# sec_board.net
KiCad netlist of a schematic drawn in EAGLE
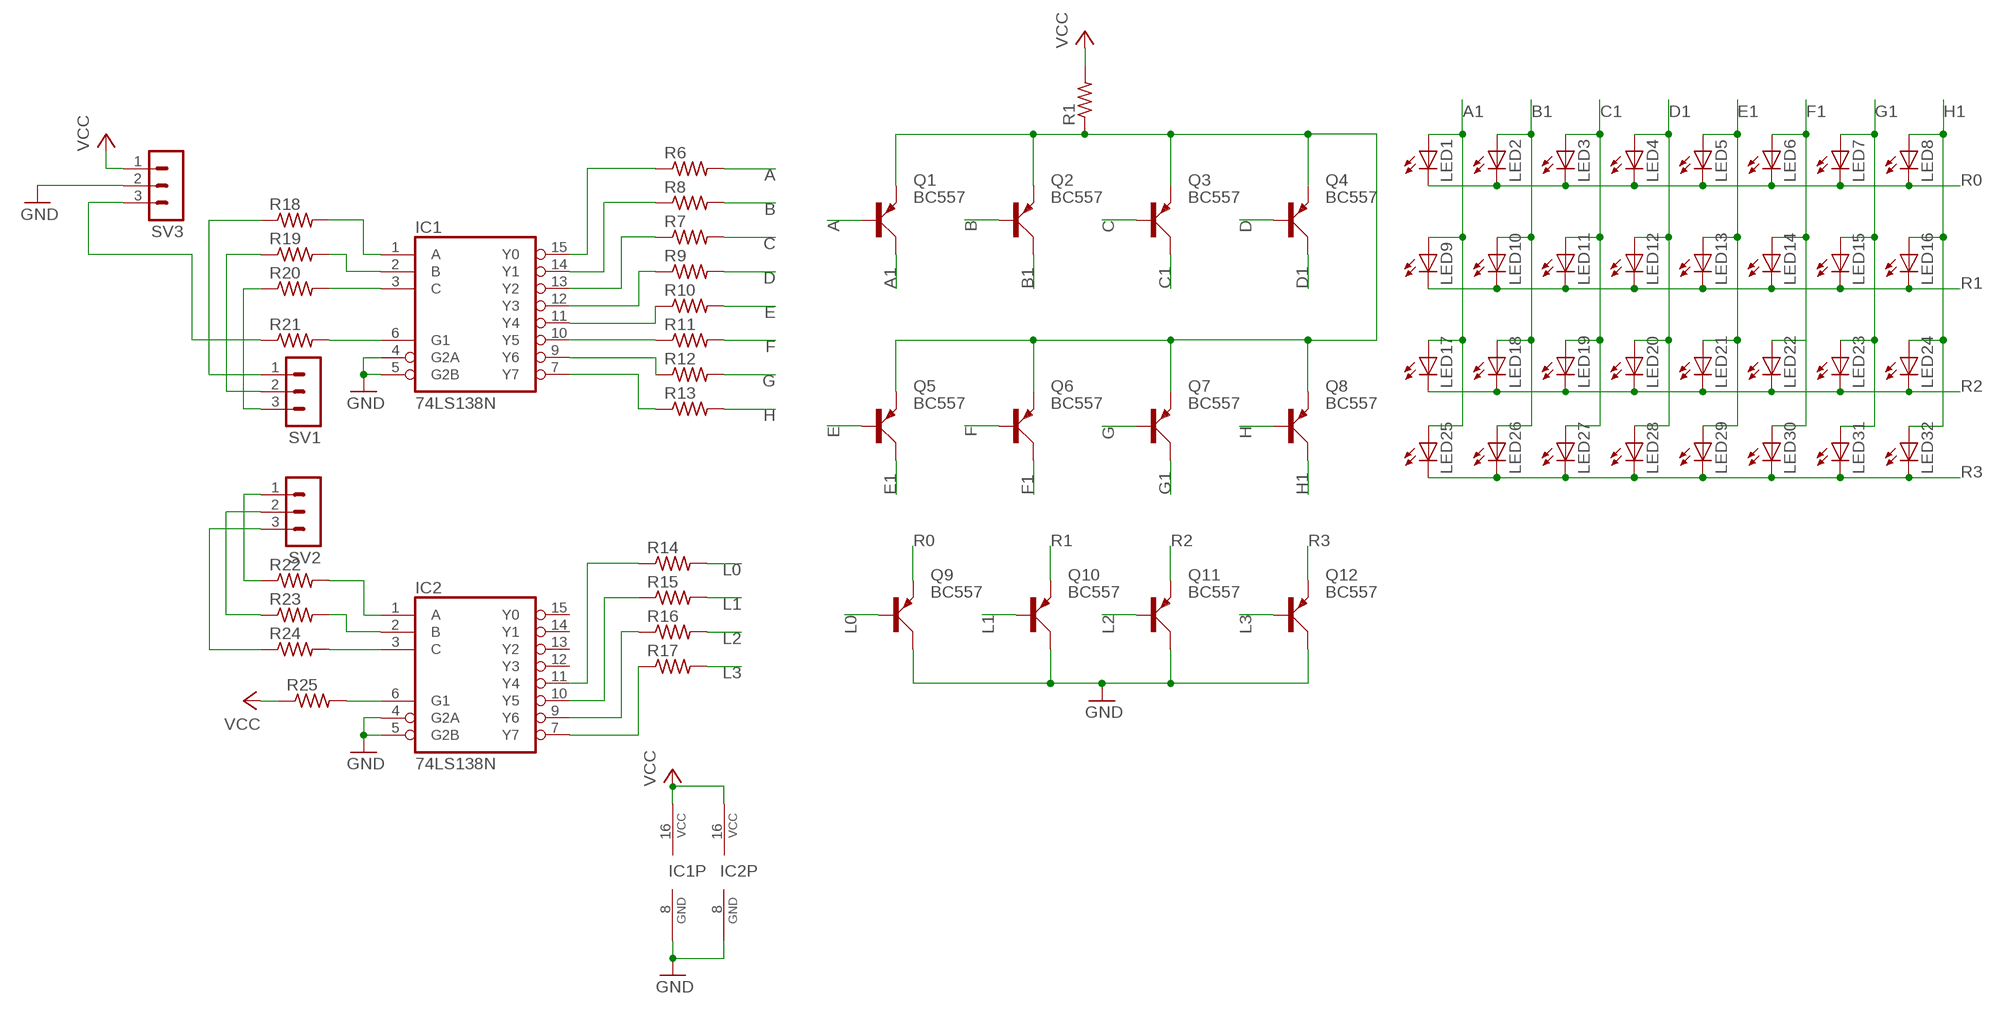
[diagram p0: schematic, sheet 1]

(export (version "E")
  (design (tool "Eeschema 10.0.6"))
  (components
    (comp (ref "IC1")
      (value "74LS138N")
      (footprint "eagle-import:DIL16")
      (libsource (lib "eagle-import") (part "74138NLS"))
    )
    (comp (ref "IC2")
      (value "74LS138N")
      (footprint "eagle-import:DIL16")
      (libsource (lib "eagle-import") (part "74138NLS"))
    )
    (comp (ref "LED1")
      (value "LED5MM")
      (footprint "eagle-import:LED5MM")
      (libsource (lib "eagle-import") (part "LED5MM"))
    )
    (comp (ref "LED2")
      (value "LED5MM")
      (footprint "eagle-import:LED5MM")
      (libsource (lib "eagle-import") (part "LED5MM"))
    )
    (comp (ref "LED3")
      (value "LED5MM")
      (footprint "eagle-import:LED5MM")
      (libsource (lib "eagle-import") (part "LED5MM"))
    )
    (comp (ref "LED4")
      (value "LED5MM")
      (footprint "eagle-import:LED5MM")
      (libsource (lib "eagle-import") (part "LED5MM"))
    )
    (comp (ref "LED5")
      (value "LED5MM")
      (footprint "eagle-import:LED5MM")
      (libsource (lib "eagle-import") (part "LED5MM"))
    )
    (comp (ref "LED6")
      (value "LED5MM")
      (footprint "eagle-import:LED5MM")
      (libsource (lib "eagle-import") (part "LED5MM"))
    )
    (comp (ref "LED7")
      (value "LED5MM")
      (footprint "eagle-import:LED5MM")
      (libsource (lib "eagle-import") (part "LED5MM"))
    )
    (comp (ref "LED8")
      (value "LED5MM")
      (footprint "eagle-import:LED5MM")
      (libsource (lib "eagle-import") (part "LED5MM"))
    )
    (comp (ref "LED9")
      (value "LED5MM")
      (footprint "eagle-import:LED5MM")
      (libsource (lib "eagle-import") (part "LED5MM"))
    )
    (comp (ref "LED10")
      (value "LED5MM")
      (footprint "eagle-import:LED5MM")
      (libsource (lib "eagle-import") (part "LED5MM"))
    )
    (comp (ref "LED11")
      (value "LED5MM")
      (footprint "eagle-import:LED5MM")
      (libsource (lib "eagle-import") (part "LED5MM"))
    )
    (comp (ref "LED12")
      (value "LED5MM")
      (footprint "eagle-import:LED5MM")
      (libsource (lib "eagle-import") (part "LED5MM"))
    )
    (comp (ref "LED13")
      (value "LED5MM")
      (footprint "eagle-import:LED5MM")
      (libsource (lib "eagle-import") (part "LED5MM"))
    )
    (comp (ref "LED14")
      (value "LED5MM")
      (footprint "eagle-import:LED5MM")
      (libsource (lib "eagle-import") (part "LED5MM"))
    )
    (comp (ref "LED15")
      (value "LED5MM")
      (footprint "eagle-import:LED5MM")
      (libsource (lib "eagle-import") (part "LED5MM"))
    )
    (comp (ref "LED16")
      (value "LED5MM")
      (footprint "eagle-import:LED5MM")
      (libsource (lib "eagle-import") (part "LED5MM"))
    )
    (comp (ref "LED17")
      (value "LED5MM")
      (footprint "eagle-import:LED5MM")
      (libsource (lib "eagle-import") (part "LED5MM"))
    )
    (comp (ref "LED18")
      (value "LED5MM")
      (footprint "eagle-import:LED5MM")
      (libsource (lib "eagle-import") (part "LED5MM"))
    )
    (comp (ref "LED19")
      (value "LED5MM")
      (footprint "eagle-import:LED5MM")
      (libsource (lib "eagle-import") (part "LED5MM"))
    )
    (comp (ref "LED20")
      (value "LED5MM")
      (footprint "eagle-import:LED5MM")
      (libsource (lib "eagle-import") (part "LED5MM"))
    )
    (comp (ref "LED21")
      (value "LED5MM")
      (footprint "eagle-import:LED5MM")
      (libsource (lib "eagle-import") (part "LED5MM"))
    )
    (comp (ref "LED22")
      (value "LED5MM")
      (footprint "eagle-import:LED5MM")
      (libsource (lib "eagle-import") (part "LED5MM"))
    )
    (comp (ref "LED23")
      (value "LED5MM")
      (footprint "eagle-import:LED5MM")
      (libsource (lib "eagle-import") (part "LED5MM"))
    )
    (comp (ref "LED24")
      (value "LED5MM")
      (footprint "eagle-import:LED5MM")
      (libsource (lib "eagle-import") (part "LED5MM"))
    )
    (comp (ref "LED25")
      (value "LED5MM")
      (footprint "eagle-import:LED5MM")
      (libsource (lib "eagle-import") (part "LED5MM"))
    )
    (comp (ref "LED26")
      (value "LED5MM")
      (footprint "eagle-import:LED5MM")
      (libsource (lib "eagle-import") (part "LED5MM"))
    )
    (comp (ref "LED27")
      (value "LED5MM")
      (footprint "eagle-import:LED5MM")
      (libsource (lib "eagle-import") (part "LED5MM"))
    )
    (comp (ref "LED28")
      (value "LED5MM")
      (footprint "eagle-import:LED5MM")
      (libsource (lib "eagle-import") (part "LED5MM"))
    )
    (comp (ref "LED29")
      (value "LED5MM")
      (footprint "eagle-import:LED5MM")
      (libsource (lib "eagle-import") (part "LED5MM"))
    )
    (comp (ref "LED30")
      (value "LED5MM")
      (footprint "eagle-import:LED5MM")
      (libsource (lib "eagle-import") (part "LED5MM"))
    )
    (comp (ref "LED31")
      (value "LED5MM")
      (footprint "eagle-import:LED5MM")
      (libsource (lib "eagle-import") (part "LED5MM"))
    )
    (comp (ref "LED32")
      (value "LED5MM")
      (footprint "eagle-import:LED5MM")
      (libsource (lib "eagle-import") (part "LED5MM"))
    )
    (comp (ref "Q1")
      (value "BC557")
      (footprint "eagle-import:SOT54A")
      (libsource (lib "eagle-import") (part "BC557"))
    )
    (comp (ref "Q2")
      (value "BC557")
      (footprint "eagle-import:SOT54A")
      (libsource (lib "eagle-import") (part "BC557"))
    )
    (comp (ref "Q3")
      (value "BC557")
      (footprint "eagle-import:SOT54A")
      (libsource (lib "eagle-import") (part "BC557"))
    )
    (comp (ref "Q4")
      (value "BC557")
      (footprint "eagle-import:SOT54A")
      (libsource (lib "eagle-import") (part "BC557"))
    )
    (comp (ref "Q5")
      (value "BC557")
      (footprint "eagle-import:SOT54A")
      (libsource (lib "eagle-import") (part "BC557"))
    )
    (comp (ref "Q6")
      (value "BC557")
      (footprint "eagle-import:SOT54A")
      (libsource (lib "eagle-import") (part "BC557"))
    )
    (comp (ref "Q7")
      (value "BC557")
      (footprint "eagle-import:SOT54A")
      (libsource (lib "eagle-import") (part "BC557"))
    )
    (comp (ref "Q8")
      (value "BC557")
      (footprint "eagle-import:SOT54A")
      (libsource (lib "eagle-import") (part "BC557"))
    )
    (comp (ref "Q9")
      (value "BC557")
      (footprint "eagle-import:SOT54A")
      (libsource (lib "eagle-import") (part "BC557"))
    )
    (comp (ref "Q10")
      (value "BC557")
      (footprint "eagle-import:SOT54A")
      (libsource (lib "eagle-import") (part "BC557"))
    )
    (comp (ref "Q11")
      (value "BC557")
      (footprint "eagle-import:SOT54A")
      (libsource (lib "eagle-import") (part "BC557"))
    )
    (comp (ref "Q12")
      (value "BC557")
      (footprint "eagle-import:SOT54A")
      (libsource (lib "eagle-import") (part "BC557"))
    )
    (comp (ref "R1")
      (value "R-US_R0805")
      (footprint "eagle-import:R0805")
      (libsource (lib "eagle-import") (part "R-US_R0805"))
    )
    (comp (ref "R6")
      (value "R-US_R0805")
      (footprint "eagle-import:R0805")
      (libsource (lib "eagle-import") (part "R-US_R0805"))
    )
    (comp (ref "R7")
      (value "R-US_R0805")
      (footprint "eagle-import:R0805")
      (libsource (lib "eagle-import") (part "R-US_R0805"))
    )
    (comp (ref "R8")
      (value "R-US_R0805")
      (footprint "eagle-import:R0805")
      (libsource (lib "eagle-import") (part "R-US_R0805"))
    )
    (comp (ref "R9")
      (value "R-US_R0805")
      (footprint "eagle-import:R0805")
      (libsource (lib "eagle-import") (part "R-US_R0805"))
    )
    (comp (ref "R10")
      (value "R-US_R0805")
      (footprint "eagle-import:R0805")
      (libsource (lib "eagle-import") (part "R-US_R0805"))
    )
    (comp (ref "R11")
      (value "R-US_R0805")
      (footprint "eagle-import:R0805")
      (libsource (lib "eagle-import") (part "R-US_R0805"))
    )
    (comp (ref "R12")
      (value "R-US_R0805")
      (footprint "eagle-import:R0805")
      (libsource (lib "eagle-import") (part "R-US_R0805"))
    )
    (comp (ref "R13")
      (value "R-US_R0805")
      (footprint "eagle-import:R0805")
      (libsource (lib "eagle-import") (part "R-US_R0805"))
    )
    (comp (ref "R14")
      (value "R-US_R0805")
      (footprint "eagle-import:R0805")
      (libsource (lib "eagle-import") (part "R-US_R0805"))
    )
    (comp (ref "R15")
      (value "R-US_R0805")
      (footprint "eagle-import:R0805")
      (libsource (lib "eagle-import") (part "R-US_R0805"))
    )
    (comp (ref "R16")
      (value "R-US_R0805")
      (footprint "eagle-import:R0805")
      (libsource (lib "eagle-import") (part "R-US_R0805"))
    )
    (comp (ref "R17")
      (value "R-US_R0805")
      (footprint "eagle-import:R0805")
      (libsource (lib "eagle-import") (part "R-US_R0805"))
    )
    (comp (ref "R18")
      (value "R-US_M0805")
      (footprint "eagle-import:M0805")
      (libsource (lib "eagle-import") (part "resistor_348_R-US_M0805"))
    )
    (comp (ref "R19")
      (value "R-US_M0805")
      (footprint "eagle-import:M0805")
      (libsource (lib "eagle-import") (part "resistor_348_R-US_M0805"))
    )
    (comp (ref "R20")
      (value "R-US_M0805")
      (footprint "eagle-import:M0805")
      (libsource (lib "eagle-import") (part "resistor_348_R-US_M0805"))
    )
    (comp (ref "R21")
      (value "R-US_M0805")
      (footprint "eagle-import:M0805")
      (libsource (lib "eagle-import") (part "resistor_348_R-US_M0805"))
    )
    (comp (ref "R22")
      (value "R-US_M0805")
      (footprint "eagle-import:M0805")
      (libsource (lib "eagle-import") (part "resistor_348_R-US_M0805"))
    )
    (comp (ref "R23")
      (value "R-US_M0805")
      (footprint "eagle-import:M0805")
      (libsource (lib "eagle-import") (part "resistor_348_R-US_M0805"))
    )
    (comp (ref "R24")
      (value "R-US_M0805")
      (footprint "eagle-import:M0805")
      (libsource (lib "eagle-import") (part "resistor_348_R-US_M0805"))
    )
    (comp (ref "R25")
      (value "R-US_M0805")
      (footprint "eagle-import:M0805")
      (libsource (lib "eagle-import") (part "resistor_348_R-US_M0805"))
    )
    (comp (ref "SV1")
      (value "MA03-1")
      (footprint "eagle-import:MA03-1")
      (libsource (lib "eagle-import") (part "MA03-1"))
    )
    (comp (ref "SV2")
      (value "MA03-1")
      (footprint "eagle-import:MA03-1")
      (libsource (lib "eagle-import") (part "MA03-1"))
    )
    (comp (ref "SV3")
      (value "MA03-1")
      (footprint "eagle-import:MA03-1")
      (libsource (lib "eagle-import") (part "MA03-1"))
    )
  )
  (nets
    (net (code "1") (name "/A") (class "Default")
      (node (ref "Q1") (pin "B") (pinfunction "B_B") (pintype "passive"))
      (node (ref "R6") (pin "2") (pinfunction "2_2") (pintype "passive"))
    )
    (net (code "2") (name "/A1") (class "Default")
      (node (ref "LED1") (pin "A") (pinfunction "A_A") (pintype "passive"))
      (node (ref "LED17") (pin "A") (pinfunction "A_A") (pintype "passive"))
      (node (ref "LED25") (pin "A") (pinfunction "A_A") (pintype "passive"))
      (node (ref "LED9") (pin "A") (pinfunction "A_A") (pintype "passive"))
      (node (ref "Q1") (pin "C") (pinfunction "C_C") (pintype "passive"))
    )
    (net (code "3") (name "/B") (class "Default")
      (node (ref "Q2") (pin "B") (pinfunction "B_B") (pintype "passive"))
      (node (ref "R8") (pin "2") (pinfunction "2_2") (pintype "passive"))
    )
    (net (code "4") (name "/B1") (class "Default")
      (node (ref "LED10") (pin "A") (pinfunction "A_A") (pintype "passive"))
      (node (ref "LED18") (pin "A") (pinfunction "A_A") (pintype "passive"))
      (node (ref "LED2") (pin "A") (pinfunction "A_A") (pintype "passive"))
      (node (ref "LED26") (pin "A") (pinfunction "A_A") (pintype "passive"))
      (node (ref "Q2") (pin "C") (pinfunction "C_C") (pintype "passive"))
    )
    (net (code "5") (name "/C") (class "Default")
      (node (ref "Q3") (pin "B") (pinfunction "B_B") (pintype "passive"))
      (node (ref "R7") (pin "2") (pinfunction "2_2") (pintype "passive"))
    )
    (net (code "6") (name "/C1") (class "Default")
      (node (ref "LED11") (pin "A") (pinfunction "A_A") (pintype "passive"))
      (node (ref "LED19") (pin "A") (pinfunction "A_A") (pintype "passive"))
      (node (ref "LED27") (pin "A") (pinfunction "A_A") (pintype "passive"))
      (node (ref "LED3") (pin "A") (pinfunction "A_A") (pintype "passive"))
      (node (ref "Q3") (pin "C") (pinfunction "C_C") (pintype "passive"))
    )
    (net (code "7") (name "/D") (class "Default")
      (node (ref "Q4") (pin "B") (pinfunction "B_B") (pintype "passive"))
      (node (ref "R9") (pin "2") (pinfunction "2_2") (pintype "passive"))
    )
    (net (code "8") (name "/D1") (class "Default")
      (node (ref "LED12") (pin "A") (pinfunction "A_A") (pintype "passive"))
      (node (ref "LED20") (pin "A") (pinfunction "A_A") (pintype "passive"))
      (node (ref "LED28") (pin "A") (pinfunction "A_A") (pintype "passive"))
      (node (ref "LED4") (pin "A") (pinfunction "A_A") (pintype "passive"))
      (node (ref "Q4") (pin "C") (pinfunction "C_C") (pintype "passive"))
    )
    (net (code "9") (name "/E") (class "Default")
      (node (ref "Q5") (pin "B") (pinfunction "B_B") (pintype "passive"))
      (node (ref "R10") (pin "2") (pinfunction "2_2") (pintype "passive"))
    )
    (net (code "10") (name "/E1") (class "Default")
      (node (ref "LED13") (pin "A") (pinfunction "A_A") (pintype "passive"))
      (node (ref "LED21") (pin "A") (pinfunction "A_A") (pintype "passive"))
      (node (ref "LED29") (pin "A") (pinfunction "A_A") (pintype "passive"))
      (node (ref "LED5") (pin "A") (pinfunction "A_A") (pintype "passive"))
      (node (ref "Q5") (pin "C") (pinfunction "C_C") (pintype "passive"))
    )
    (net (code "11") (name "/F") (class "Default")
      (node (ref "Q6") (pin "B") (pinfunction "B_B") (pintype "passive"))
      (node (ref "R11") (pin "2") (pinfunction "2_2") (pintype "passive"))
    )
    (net (code "12") (name "/F1") (class "Default")
      (node (ref "LED14") (pin "A") (pinfunction "A_A") (pintype "passive"))
      (node (ref "LED22") (pin "A") (pinfunction "A_A") (pintype "passive"))
      (node (ref "LED30") (pin "A") (pinfunction "A_A") (pintype "passive"))
      (node (ref "LED6") (pin "A") (pinfunction "A_A") (pintype "passive"))
      (node (ref "Q6") (pin "C") (pinfunction "C_C") (pintype "passive"))
    )
    (net (code "13") (name "/G") (class "Default")
      (node (ref "Q7") (pin "B") (pinfunction "B_B") (pintype "passive"))
      (node (ref "R12") (pin "2") (pinfunction "2_2") (pintype "passive"))
    )
    (net (code "14") (name "/G1") (class "Default")
      (node (ref "LED15") (pin "A") (pinfunction "A_A") (pintype "passive"))
      (node (ref "LED23") (pin "A") (pinfunction "A_A") (pintype "passive"))
      (node (ref "LED31") (pin "A") (pinfunction "A_A") (pintype "passive"))
      (node (ref "LED7") (pin "A") (pinfunction "A_A") (pintype "passive"))
      (node (ref "Q7") (pin "C") (pinfunction "C_C") (pintype "passive"))
    )
    (net (code "15") (name "/H") (class "Default")
      (node (ref "Q8") (pin "B") (pinfunction "B_B") (pintype "passive"))
      (node (ref "R13") (pin "2") (pinfunction "2_2") (pintype "passive"))
    )
    (net (code "16") (name "/H1") (class "Default")
      (node (ref "LED16") (pin "A") (pinfunction "A_A") (pintype "passive"))
      (node (ref "LED24") (pin "A") (pinfunction "A_A") (pintype "passive"))
      (node (ref "LED32") (pin "A") (pinfunction "A_A") (pintype "passive"))
      (node (ref "LED8") (pin "A") (pinfunction "A_A") (pintype "passive"))
      (node (ref "Q8") (pin "C") (pinfunction "C_C") (pintype "passive"))
    )
    (net (code "17") (name "/L0") (class "Default")
      (node (ref "Q9") (pin "B") (pinfunction "B_B") (pintype "passive"))
      (node (ref "R14") (pin "2") (pinfunction "2_2") (pintype "passive"))
    )
    (net (code "18") (name "/L1") (class "Default")
      (node (ref "Q10") (pin "B") (pinfunction "B_B") (pintype "passive"))
      (node (ref "R15") (pin "2") (pinfunction "2_2") (pintype "passive"))
    )
    (net (code "19") (name "/L2") (class "Default")
      (node (ref "Q11") (pin "B") (pinfunction "B_B") (pintype "passive"))
      (node (ref "R16") (pin "2") (pinfunction "2_2") (pintype "passive"))
    )
    (net (code "20") (name "/L3") (class "Default")
      (node (ref "Q12") (pin "B") (pinfunction "B_B") (pintype "passive"))
      (node (ref "R17") (pin "2") (pinfunction "2_2") (pintype "passive"))
    )
    (net (code "21") (name "/R0") (class "Default")
      (node (ref "LED1") (pin "K") (pinfunction "C_K") (pintype "passive"))
      (node (ref "LED2") (pin "K") (pinfunction "C_K") (pintype "passive"))
      (node (ref "LED3") (pin "K") (pinfunction "C_K") (pintype "passive"))
      (node (ref "LED4") (pin "K") (pinfunction "C_K") (pintype "passive"))
      (node (ref "LED5") (pin "K") (pinfunction "C_K") (pintype "passive"))
      (node (ref "LED6") (pin "K") (pinfunction "C_K") (pintype "passive"))
      (node (ref "LED7") (pin "K") (pinfunction "C_K") (pintype "passive"))
      (node (ref "LED8") (pin "K") (pinfunction "C_K") (pintype "passive"))
      (node (ref "Q9") (pin "E") (pinfunction "E_E") (pintype "passive"))
    )
    (net (code "22") (name "/R1") (class "Default")
      (node (ref "LED10") (pin "K") (pinfunction "C_K") (pintype "passive"))
      (node (ref "LED11") (pin "K") (pinfunction "C_K") (pintype "passive"))
      (node (ref "LED12") (pin "K") (pinfunction "C_K") (pintype "passive"))
      (node (ref "LED13") (pin "K") (pinfunction "C_K") (pintype "passive"))
      (node (ref "LED14") (pin "K") (pinfunction "C_K") (pintype "passive"))
      (node (ref "LED15") (pin "K") (pinfunction "C_K") (pintype "passive"))
      (node (ref "LED16") (pin "K") (pinfunction "C_K") (pintype "passive"))
      (node (ref "LED9") (pin "K") (pinfunction "C_K") (pintype "passive"))
      (node (ref "Q10") (pin "E") (pinfunction "E_E") (pintype "passive"))
    )
    (net (code "23") (name "/R2") (class "Default")
      (node (ref "LED17") (pin "K") (pinfunction "C_K") (pintype "passive"))
      (node (ref "LED18") (pin "K") (pinfunction "C_K") (pintype "passive"))
      (node (ref "LED19") (pin "K") (pinfunction "C_K") (pintype "passive"))
      (node (ref "LED20") (pin "K") (pinfunction "C_K") (pintype "passive"))
      (node (ref "LED21") (pin "K") (pinfunction "C_K") (pintype "passive"))
      (node (ref "LED22") (pin "K") (pinfunction "C_K") (pintype "passive"))
      (node (ref "LED23") (pin "K") (pinfunction "C_K") (pintype "passive"))
      (node (ref "LED24") (pin "K") (pinfunction "C_K") (pintype "passive"))
      (node (ref "Q11") (pin "E") (pinfunction "E_E") (pintype "passive"))
    )
    (net (code "24") (name "/R3") (class "Default")
      (node (ref "LED25") (pin "K") (pinfunction "C_K") (pintype "passive"))
      (node (ref "LED26") (pin "K") (pinfunction "C_K") (pintype "passive"))
      (node (ref "LED27") (pin "K") (pinfunction "C_K") (pintype "passive"))
      (node (ref "LED28") (pin "K") (pinfunction "C_K") (pintype "passive"))
      (node (ref "LED29") (pin "K") (pinfunction "C_K") (pintype "passive"))
      (node (ref "LED30") (pin "K") (pinfunction "C_K") (pintype "passive"))
      (node (ref "LED31") (pin "K") (pinfunction "C_K") (pintype "passive"))
      (node (ref "LED32") (pin "K") (pinfunction "C_K") (pintype "passive"))
      (node (ref "Q12") (pin "E") (pinfunction "E_E") (pintype "passive"))
    )
    (net (code "25") (name "GND") (class "Default")
      (node (ref "IC1") (pin "4") (pinfunction "G2A_4") (pintype "input"))
      (node (ref "IC1") (pin "5") (pinfunction "G2B_5") (pintype "input"))
      (node (ref "IC1") (pin "8") (pinfunction "GND_8") (pintype "power_in"))
      (node (ref "IC2") (pin "4") (pinfunction "G2A_4") (pintype "input"))
      (node (ref "IC2") (pin "5") (pinfunction "G2B_5") (pintype "input"))
      (node (ref "IC2") (pin "8") (pinfunction "GND_8") (pintype "power_in"))
      (node (ref "Q10") (pin "C") (pinfunction "C_C") (pintype "passive"))
      (node (ref "Q11") (pin "C") (pinfunction "C_C") (pintype "passive"))
      (node (ref "Q12") (pin "C") (pinfunction "C_C") (pintype "passive"))
      (node (ref "Q9") (pin "C") (pinfunction "C_C") (pintype "passive"))
      (node (ref "SV3") (pin "2") (pinfunction "2_2") (pintype "passive"))
    )
    (net (code "26") (name "Net-(IC1A-A)") (class "Default")
      (node (ref "IC1") (pin "1") (pinfunction "A_1") (pintype "input"))
      (node (ref "R18") (pin "2") (pinfunction "2_2") (pintype "passive"))
    )
    (net (code "27") (name "Net-(IC1A-B)") (class "Default")
      (node (ref "IC1") (pin "2") (pinfunction "B_2") (pintype "input"))
      (node (ref "R19") (pin "2") (pinfunction "2_2") (pintype "passive"))
    )
    (net (code "28") (name "Net-(IC1A-C)") (class "Default")
      (node (ref "IC1") (pin "3") (pinfunction "C_3") (pintype "input"))
      (node (ref "R20") (pin "2") (pinfunction "2_2") (pintype "passive"))
    )
    (net (code "29") (name "Net-(IC1A-G1)") (class "Default")
      (node (ref "IC1") (pin "6") (pinfunction "G1_6") (pintype "input"))
      (node (ref "R21") (pin "2") (pinfunction "2_2") (pintype "passive"))
    )
    (net (code "30") (name "Net-(IC1A-Y0)") (class "Default")
      (node (ref "IC1") (pin "15") (pinfunction "Y0_15") (pintype "output"))
      (node (ref "R6") (pin "1") (pinfunction "1_1") (pintype "passive"))
    )
    (net (code "31") (name "Net-(IC1A-Y1)") (class "Default")
      (node (ref "IC1") (pin "14") (pinfunction "Y1_14") (pintype "output"))
      (node (ref "R8") (pin "1") (pinfunction "1_1") (pintype "passive"))
    )
    (net (code "32") (name "Net-(IC1A-Y2)") (class "Default")
      (node (ref "IC1") (pin "13") (pinfunction "Y2_13") (pintype "output"))
      (node (ref "R7") (pin "1") (pinfunction "1_1") (pintype "passive"))
    )
    (net (code "33") (name "Net-(IC1A-Y3)") (class "Default")
      (node (ref "IC1") (pin "12") (pinfunction "Y3_12") (pintype "output"))
      (node (ref "R9") (pin "1") (pinfunction "1_1") (pintype "passive"))
    )
    (net (code "34") (name "Net-(IC1A-Y4)") (class "Default")
      (node (ref "IC1") (pin "11") (pinfunction "Y4_11") (pintype "output"))
      (node (ref "R10") (pin "1") (pinfunction "1_1") (pintype "passive"))
    )
    (net (code "35") (name "Net-(IC1A-Y5)") (class "Default")
      (node (ref "IC1") (pin "10") (pinfunction "Y5_10") (pintype "output"))
      (node (ref "R11") (pin "1") (pinfunction "1_1") (pintype "passive"))
    )
    (net (code "36") (name "Net-(IC1A-Y6)") (class "Default")
      (node (ref "IC1") (pin "9") (pinfunction "Y6_9") (pintype "output"))
      (node (ref "R12") (pin "1") (pinfunction "1_1") (pintype "passive"))
    )
    (net (code "37") (name "Net-(IC1A-Y7)") (class "Default")
      (node (ref "IC1") (pin "7") (pinfunction "Y7_7") (pintype "output"))
      (node (ref "R13") (pin "1") (pinfunction "1_1") (pintype "passive"))
    )
    (net (code "38") (name "Net-(IC2A-A)") (class "Default")
      (node (ref "IC2") (pin "1") (pinfunction "A_1") (pintype "input"))
      (node (ref "R22") (pin "2") (pinfunction "2_2") (pintype "passive"))
    )
    (net (code "39") (name "Net-(IC2A-B)") (class "Default")
      (node (ref "IC2") (pin "2") (pinfunction "B_2") (pintype "input"))
      (node (ref "R23") (pin "2") (pinfunction "2_2") (pintype "passive"))
    )
    (net (code "40") (name "Net-(IC2A-C)") (class "Default")
      (node (ref "IC2") (pin "3") (pinfunction "C_3") (pintype "input"))
      (node (ref "R24") (pin "2") (pinfunction "2_2") (pintype "passive"))
    )
    (net (code "41") (name "Net-(IC2A-G1)") (class "Default")
      (node (ref "IC2") (pin "6") (pinfunction "G1_6") (pintype "input"))
      (node (ref "R25") (pin "2") (pinfunction "2_2") (pintype "passive"))
    )
    (net (code "42") (name "Net-(IC2A-Y4)") (class "Default")
      (node (ref "IC2") (pin "11") (pinfunction "Y4_11") (pintype "output"))
      (node (ref "R14") (pin "1") (pinfunction "1_1") (pintype "passive"))
    )
    (net (code "43") (name "Net-(IC2A-Y5)") (class "Default")
      (node (ref "IC2") (pin "10") (pinfunction "Y5_10") (pintype "output"))
      (node (ref "R15") (pin "1") (pinfunction "1_1") (pintype "passive"))
    )
    (net (code "44") (name "Net-(IC2A-Y6)") (class "Default")
      (node (ref "IC2") (pin "9") (pinfunction "Y6_9") (pintype "output"))
      (node (ref "R16") (pin "1") (pinfunction "1_1") (pintype "passive"))
    )
    (net (code "45") (name "Net-(IC2A-Y7)") (class "Default")
      (node (ref "IC2") (pin "7") (pinfunction "Y7_7") (pintype "output"))
      (node (ref "R17") (pin "1") (pinfunction "1_1") (pintype "passive"))
    )
    (net (code "46") (name "Net-(Q1-PadE)") (class "Default")
      (node (ref "Q1") (pin "E") (pinfunction "E_E") (pintype "passive"))
      (node (ref "Q2") (pin "E") (pinfunction "E_E") (pintype "passive"))
      (node (ref "Q3") (pin "E") (pinfunction "E_E") (pintype "passive"))
      (node (ref "Q4") (pin "E") (pinfunction "E_E") (pintype "passive"))
      (node (ref "Q5") (pin "E") (pinfunction "E_E") (pintype "passive"))
      (node (ref "Q6") (pin "E") (pinfunction "E_E") (pintype "passive"))
      (node (ref "Q7") (pin "E") (pinfunction "E_E") (pintype "passive"))
      (node (ref "Q8") (pin "E") (pinfunction "E_E") (pintype "passive"))
      (node (ref "R1") (pin "1") (pinfunction "1_1") (pintype "passive"))
    )
    (net (code "47") (name "Net-(R18-Pad1)") (class "Default")
      (node (ref "R18") (pin "1") (pinfunction "1_1") (pintype "passive"))
      (node (ref "SV1") (pin "1") (pinfunction "1_1") (pintype "passive"))
    )
    (net (code "48") (name "Net-(R19-Pad1)") (class "Default")
      (node (ref "R19") (pin "1") (pinfunction "1_1") (pintype "passive"))
      (node (ref "SV1") (pin "2") (pinfunction "2_2") (pintype "passive"))
    )
    (net (code "49") (name "Net-(R20-Pad1)") (class "Default")
      (node (ref "R20") (pin "1") (pinfunction "1_1") (pintype "passive"))
      (node (ref "SV1") (pin "3") (pinfunction "3_3") (pintype "passive"))
    )
    (net (code "50") (name "Net-(R21-Pad1)") (class "Default")
      (node (ref "R21") (pin "1") (pinfunction "1_1") (pintype "passive"))
      (node (ref "SV3") (pin "3") (pinfunction "3_3") (pintype "passive"))
    )
    (net (code "51") (name "Net-(R22-Pad1)") (class "Default")
      (node (ref "R22") (pin "1") (pinfunction "1_1") (pintype "passive"))
      (node (ref "SV2") (pin "1") (pinfunction "1_1") (pintype "passive"))
    )
    (net (code "52") (name "Net-(R23-Pad1)") (class "Default")
      (node (ref "R23") (pin "1") (pinfunction "1_1") (pintype "passive"))
      (node (ref "SV2") (pin "2") (pinfunction "2_2") (pintype "passive"))
    )
    (net (code "53") (name "Net-(R24-Pad1)") (class "Default")
      (node (ref "R24") (pin "1") (pinfunction "1_1") (pintype "passive"))
      (node (ref "SV2") (pin "3") (pinfunction "3_3") (pintype "passive"))
    )
    (net (code "54") (name "VCC") (class "Default")
      (node (ref "IC1") (pin "16") (pinfunction "VCC_16") (pintype "power_in"))
      (node (ref "IC2") (pin "16") (pinfunction "VCC_16") (pintype "power_in"))
      (node (ref "R1") (pin "2") (pinfunction "2_2") (pintype "passive"))
      (node (ref "R25") (pin "1") (pinfunction "1_1") (pintype "passive"))
      (node (ref "SV3") (pin "1") (pinfunction "1_1") (pintype "passive"))
    )
    (net (code "55") (name "unconnected-(IC2A-Y0-Pad15)") (class "Default")
      (node (ref "IC2") (pin "15") (pinfunction "Y0_15") (pintype "output"))
    )
    (net (code "56") (name "unconnected-(IC2A-Y1-Pad14)") (class "Default")
      (node (ref "IC2") (pin "14") (pinfunction "Y1_14") (pintype "output"))
    )
    (net (code "57") (name "unconnected-(IC2A-Y2-Pad13)") (class "Default")
      (node (ref "IC2") (pin "13") (pinfunction "Y2_13") (pintype "output"))
    )
    (net (code "58") (name "unconnected-(IC2A-Y3-Pad12)") (class "Default")
      (node (ref "IC2") (pin "12") (pinfunction "Y3_12") (pintype "output"))
    )
  )
)
